# PCB-SSB-4x2.net
KiCad netlist of a schematic drawn in EAGLE
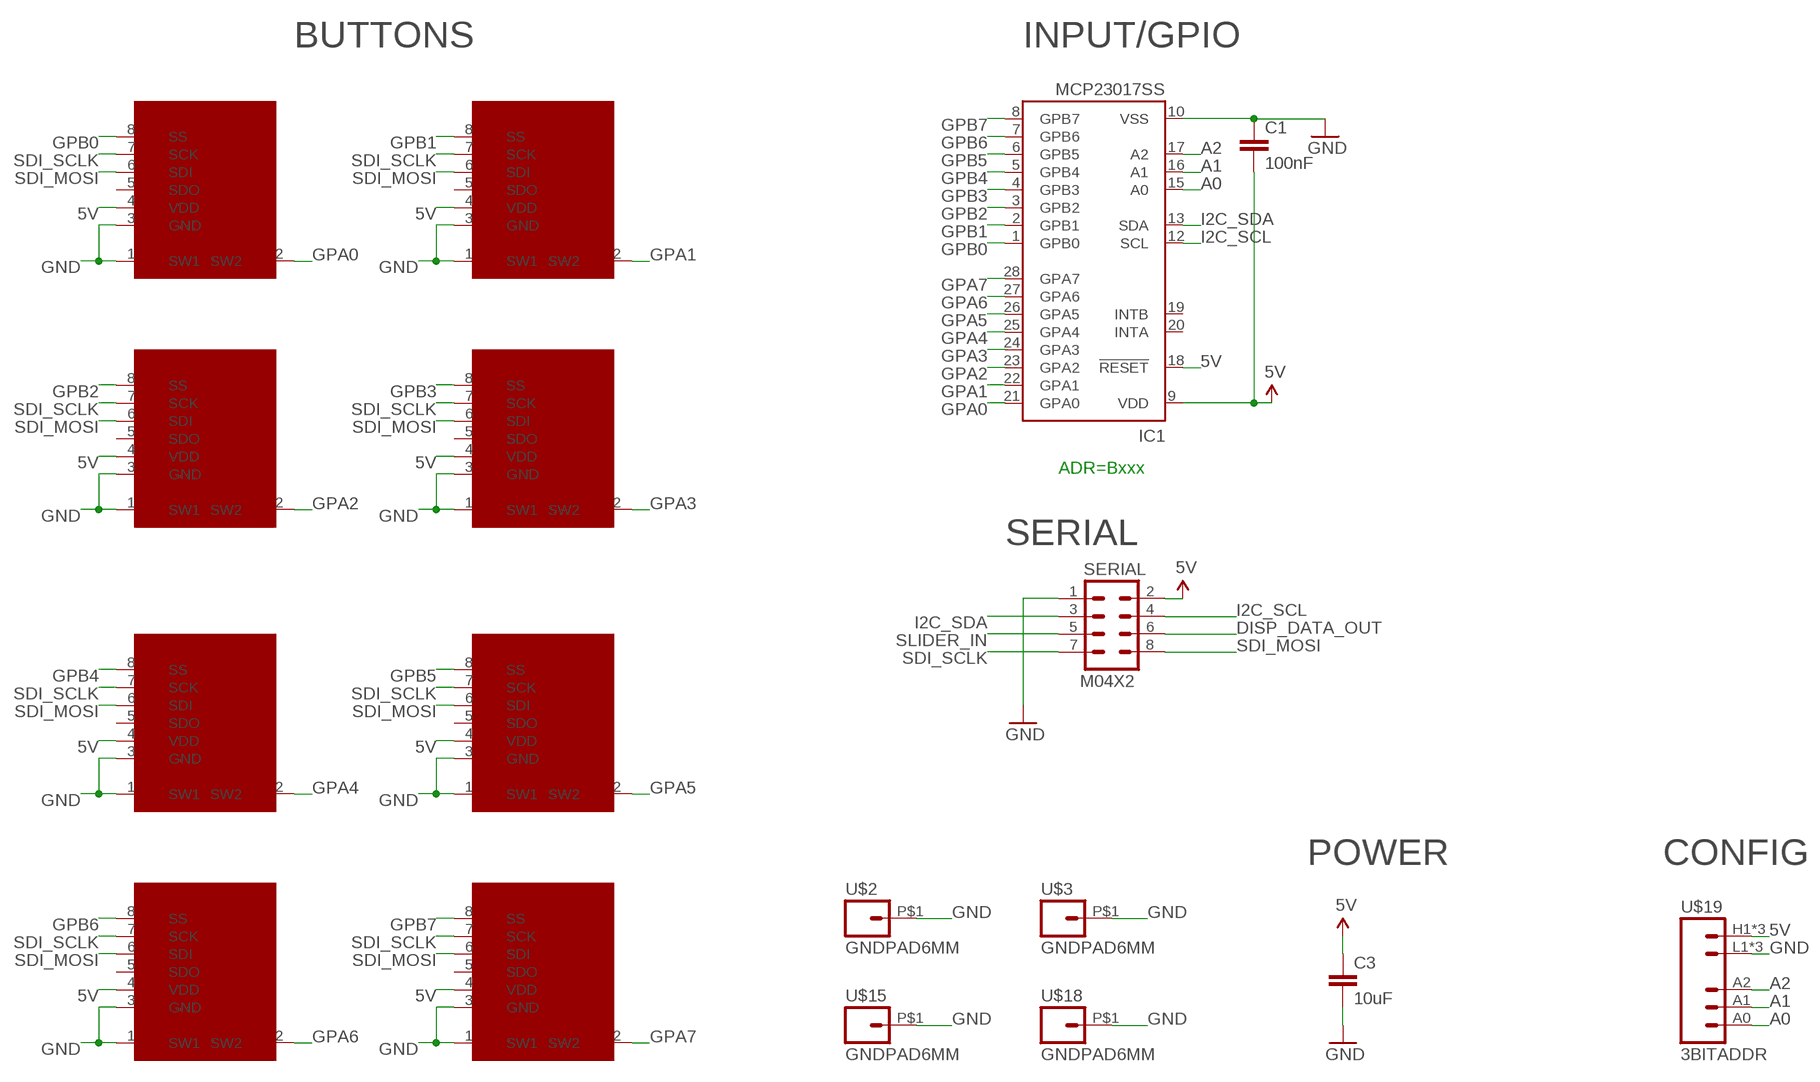
[diagram p0: schematic, sheet 1]

(export (version "E")
  (design (tool "Eeschema 10.0.6"))
  (components
    (comp (ref "C1")
      (value "100nF")
      (footprint "eagle-import:0603-CAP")
      (libsource (lib "eagle-import") (part "CAP0603-CAP"))
    )
    (comp (ref "C3")
      (value "10uF")
      (footprint "eagle-import:0805")
      (libsource (lib "eagle-import") (part "CAP0805"))
    )
    (comp (ref "IC1")
      (value "MCP23017SS")
      (footprint "eagle-import:SSOP28")
      (fields
        (field (name "MF") "MICROCHIP")
        (field (name "MPN") "MCP23017-E/SS")
        (field (name "MPN_1") "MCP23017-E/SS")
        (field (name "OC_FARNELL") "1467674")
        (field (name "OC_NEWARK") "31K2960")
      )
      (libsource (lib "eagle-import") (part "MCP23017SS"))
    )
    (comp (ref "SERIAL")
      (value "M04X2")
      (footprint "eagle-import:2X4")
      (libsource (lib "eagle-import") (part "M04X2"))
    )
    (comp (ref "SSW1")
      (value "SMART_SWITCHSMART_SWITCH_8PIN")
      (footprint "eagle-import:SMART_SWITCH")
      (libsource (lib "eagle-import") (part "SMART_SWITCHSMART_SWITCH_8PIN"))
    )
    (comp (ref "SSW2")
      (value "SMART_SWITCHSMART_SWITCH_8PIN")
      (footprint "eagle-import:SMART_SWITCH")
      (libsource (lib "eagle-import") (part "SMART_SWITCHSMART_SWITCH_8PIN"))
    )
    (comp (ref "SSW3")
      (value "SMART_SWITCHSMART_SWITCH_8PIN")
      (footprint "eagle-import:SMART_SWITCH")
      (libsource (lib "eagle-import") (part "SMART_SWITCHSMART_SWITCH_8PIN"))
    )
    (comp (ref "SSW4")
      (value "SMART_SWITCHSMART_SWITCH_8PIN")
      (footprint "eagle-import:SMART_SWITCH")
      (libsource (lib "eagle-import") (part "SMART_SWITCHSMART_SWITCH_8PIN"))
    )
    (comp (ref "SSW5")
      (value "SMART_SWITCHSMART_SWITCH_8PIN")
      (footprint "eagle-import:SMART_SWITCH")
      (libsource (lib "eagle-import") (part "SMART_SWITCHSMART_SWITCH_8PIN"))
    )
    (comp (ref "SSW6")
      (value "SMART_SWITCHSMART_SWITCH_8PIN")
      (footprint "eagle-import:SMART_SWITCH")
      (libsource (lib "eagle-import") (part "SMART_SWITCHSMART_SWITCH_8PIN"))
    )
    (comp (ref "SSW7")
      (value "SMART_SWITCHSMART_SWITCH_8PIN")
      (footprint "eagle-import:SMART_SWITCH")
      (libsource (lib "eagle-import") (part "SMART_SWITCHSMART_SWITCH_8PIN"))
    )
    (comp (ref "SSW8")
      (value "SMART_SWITCHSMART_SWITCH_8PIN")
      (footprint "eagle-import:SMART_SWITCH")
      (libsource (lib "eagle-import") (part "SMART_SWITCHSMART_SWITCH_8PIN"))
    )
    (comp (ref "U$2")
      (value "GNDPAD6MM")
      (footprint "eagle-import:3.2MMPAD6MM")
      (libsource (lib "eagle-import") (part "GNDPAD6MM"))
    )
    (comp (ref "U$3")
      (value "GNDPAD6MM")
      (footprint "eagle-import:3.2MMPAD6MM")
      (libsource (lib "eagle-import") (part "GNDPAD6MM"))
    )
    (comp (ref "U$15")
      (value "GNDPAD6MM")
      (footprint "eagle-import:3.2MMPAD6MM")
      (libsource (lib "eagle-import") (part "GNDPAD6MM"))
    )
    (comp (ref "U$18")
      (value "GNDPAD6MM")
      (footprint "eagle-import:3.2MMPAD6MM")
      (libsource (lib "eagle-import") (part "GNDPAD6MM"))
    )
    (comp (ref "U$19")
      (value "3BITADDR")
      (footprint "eagle-import:3BITADDR")
      (libsource (lib "eagle-import") (part "3BITADDR"))
    )
  )
  (nets
    (net (code "1") (name "/A0") (class "Default")
      (node (ref "IC1") (pin "15") (pinfunction "A0_15") (pintype "input"))
      (node (ref "U$19") (pin "A0") (pinfunction "A0_A0") (pintype "passive"))
    )
    (net (code "2") (name "/A1") (class "Default")
      (node (ref "IC1") (pin "16") (pinfunction "A1_16") (pintype "input"))
      (node (ref "U$19") (pin "A1") (pinfunction "A1_A1") (pintype "passive"))
    )
    (net (code "3") (name "/A2") (class "Default")
      (node (ref "IC1") (pin "17") (pinfunction "A2_17") (pintype "input"))
      (node (ref "U$19") (pin "A2") (pinfunction "A2_A2") (pintype "passive"))
    )
    (net (code "4") (name "/DISP_DATA_OUT") (class "Default")
      (node (ref "SERIAL") (pin "6") (pinfunction "6_6") (pintype "passive"))
    )
    (net (code "5") (name "/GPA0") (class "Default")
      (node (ref "IC1") (pin "21") (pinfunction "GPA0_21") (pintype "bidirectional"))
      (node (ref "SSW1") (pin "2") (pinfunction "SW2_2") (pintype "bidirectional"))
    )
    (net (code "6") (name "/GPA1") (class "Default")
      (node (ref "IC1") (pin "22") (pinfunction "GPA1_22") (pintype "bidirectional"))
      (node (ref "SSW2") (pin "2") (pinfunction "SW2_2") (pintype "bidirectional"))
    )
    (net (code "7") (name "/GPA2") (class "Default")
      (node (ref "IC1") (pin "23") (pinfunction "GPA2_23") (pintype "bidirectional"))
      (node (ref "SSW3") (pin "2") (pinfunction "SW2_2") (pintype "bidirectional"))
    )
    (net (code "8") (name "/GPA3") (class "Default")
      (node (ref "IC1") (pin "24") (pinfunction "GPA3_24") (pintype "bidirectional"))
      (node (ref "SSW4") (pin "2") (pinfunction "SW2_2") (pintype "bidirectional"))
    )
    (net (code "9") (name "/GPA4") (class "Default")
      (node (ref "IC1") (pin "25") (pinfunction "GPA4_25") (pintype "bidirectional"))
      (node (ref "SSW5") (pin "2") (pinfunction "SW2_2") (pintype "bidirectional"))
    )
    (net (code "10") (name "/GPA5") (class "Default")
      (node (ref "IC1") (pin "26") (pinfunction "GPA5_26") (pintype "bidirectional"))
      (node (ref "SSW6") (pin "2") (pinfunction "SW2_2") (pintype "bidirectional"))
    )
    (net (code "11") (name "/GPA6") (class "Default")
      (node (ref "IC1") (pin "27") (pinfunction "GPA6_27") (pintype "bidirectional"))
      (node (ref "SSW7") (pin "2") (pinfunction "SW2_2") (pintype "bidirectional"))
    )
    (net (code "12") (name "/GPA7") (class "Default")
      (node (ref "IC1") (pin "28") (pinfunction "GPA7_28") (pintype "bidirectional"))
      (node (ref "SSW8") (pin "2") (pinfunction "SW2_2") (pintype "bidirectional"))
    )
    (net (code "13") (name "/GPB0") (class "Default")
      (node (ref "IC1") (pin "1") (pinfunction "GPB0_1") (pintype "bidirectional"))
      (node (ref "SSW1") (pin "8") (pinfunction "SS_8") (pintype "bidirectional"))
    )
    (net (code "14") (name "/GPB1") (class "Default")
      (node (ref "IC1") (pin "2") (pinfunction "GPB1_2") (pintype "bidirectional"))
      (node (ref "SSW2") (pin "8") (pinfunction "SS_8") (pintype "bidirectional"))
    )
    (net (code "15") (name "/GPB2") (class "Default")
      (node (ref "IC1") (pin "3") (pinfunction "GPB2_3") (pintype "bidirectional"))
      (node (ref "SSW3") (pin "8") (pinfunction "SS_8") (pintype "bidirectional"))
    )
    (net (code "16") (name "/GPB3") (class "Default")
      (node (ref "IC1") (pin "4") (pinfunction "GPB3_4") (pintype "bidirectional"))
      (node (ref "SSW4") (pin "8") (pinfunction "SS_8") (pintype "bidirectional"))
    )
    (net (code "17") (name "/GPB4") (class "Default")
      (node (ref "IC1") (pin "5") (pinfunction "GPB4_5") (pintype "bidirectional"))
      (node (ref "SSW5") (pin "8") (pinfunction "SS_8") (pintype "bidirectional"))
    )
    (net (code "18") (name "/GPB5") (class "Default")
      (node (ref "IC1") (pin "6") (pinfunction "GPB5_6") (pintype "bidirectional"))
      (node (ref "SSW6") (pin "8") (pinfunction "SS_8") (pintype "bidirectional"))
    )
    (net (code "19") (name "/GPB6") (class "Default")
      (node (ref "IC1") (pin "7") (pinfunction "GPB6_7") (pintype "bidirectional"))
      (node (ref "SSW7") (pin "8") (pinfunction "SS_8") (pintype "bidirectional"))
    )
    (net (code "20") (name "/GPB7") (class "Default")
      (node (ref "IC1") (pin "8") (pinfunction "GPB7_8") (pintype "bidirectional"))
      (node (ref "SSW8") (pin "8") (pinfunction "SS_8") (pintype "bidirectional"))
    )
    (net (code "21") (name "/I2C_SCL") (class "Default")
      (node (ref "IC1") (pin "12") (pinfunction "SCL_12") (pintype "input"))
      (node (ref "SERIAL") (pin "4") (pinfunction "4_4") (pintype "passive"))
    )
    (net (code "22") (name "/I2C_SDA") (class "Default")
      (node (ref "IC1") (pin "13") (pinfunction "SDA_13") (pintype "bidirectional"))
      (node (ref "SERIAL") (pin "3") (pinfunction "3_3") (pintype "passive"))
    )
    (net (code "23") (name "/SDI_MOSI") (class "Default")
      (node (ref "SERIAL") (pin "8") (pinfunction "8_8") (pintype "passive"))
      (node (ref "SSW1") (pin "6") (pinfunction "SDI_6") (pintype "bidirectional"))
      (node (ref "SSW2") (pin "6") (pinfunction "SDI_6") (pintype "bidirectional"))
      (node (ref "SSW3") (pin "6") (pinfunction "SDI_6") (pintype "bidirectional"))
      (node (ref "SSW4") (pin "6") (pinfunction "SDI_6") (pintype "bidirectional"))
      (node (ref "SSW5") (pin "6") (pinfunction "SDI_6") (pintype "bidirectional"))
      (node (ref "SSW6") (pin "6") (pinfunction "SDI_6") (pintype "bidirectional"))
      (node (ref "SSW7") (pin "6") (pinfunction "SDI_6") (pintype "bidirectional"))
      (node (ref "SSW8") (pin "6") (pinfunction "SDI_6") (pintype "bidirectional"))
    )
    (net (code "24") (name "/SDI_SCLK") (class "Default")
      (node (ref "SERIAL") (pin "7") (pinfunction "7_7") (pintype "passive"))
      (node (ref "SSW1") (pin "7") (pinfunction "SCK_7") (pintype "bidirectional"))
      (node (ref "SSW2") (pin "7") (pinfunction "SCK_7") (pintype "bidirectional"))
      (node (ref "SSW3") (pin "7") (pinfunction "SCK_7") (pintype "bidirectional"))
      (node (ref "SSW4") (pin "7") (pinfunction "SCK_7") (pintype "bidirectional"))
      (node (ref "SSW5") (pin "7") (pinfunction "SCK_7") (pintype "bidirectional"))
      (node (ref "SSW6") (pin "7") (pinfunction "SCK_7") (pintype "bidirectional"))
      (node (ref "SSW7") (pin "7") (pinfunction "SCK_7") (pintype "bidirectional"))
      (node (ref "SSW8") (pin "7") (pinfunction "SCK_7") (pintype "bidirectional"))
    )
    (net (code "25") (name "/SLIDER_IN") (class "Default")
      (node (ref "SERIAL") (pin "5") (pinfunction "5_5") (pintype "passive"))
    )
    (net (code "26") (name "5V") (class "Default")
      (node (ref "C1") (pin "2") (pinfunction "2_2") (pintype "passive"))
      (node (ref "C3") (pin "1") (pinfunction "1_1") (pintype "passive"))
      (node (ref "IC1") (pin "18") (pinfunction "~{RESET}_18") (pintype "input"))
      (node (ref "IC1") (pin "9") (pinfunction "VDD_9") (pintype "power_in"))
      (node (ref "SERIAL") (pin "2") (pinfunction "2_2") (pintype "passive"))
      (node (ref "SSW1") (pin "4") (pinfunction "VDD_4") (pintype "bidirectional"))
      (node (ref "SSW2") (pin "4") (pinfunction "VDD_4") (pintype "bidirectional"))
      (node (ref "SSW3") (pin "4") (pinfunction "VDD_4") (pintype "bidirectional"))
      (node (ref "SSW4") (pin "4") (pinfunction "VDD_4") (pintype "bidirectional"))
      (node (ref "SSW5") (pin "4") (pinfunction "VDD_4") (pintype "bidirectional"))
      (node (ref "SSW6") (pin "4") (pinfunction "VDD_4") (pintype "bidirectional"))
      (node (ref "SSW7") (pin "4") (pinfunction "VDD_4") (pintype "bidirectional"))
      (node (ref "SSW8") (pin "4") (pinfunction "VDD_4") (pintype "bidirectional"))
      (node (ref "U$19") (pin "H1") (pinfunction "VCC_H1") (pintype "passive"))
      (node (ref "U$19") (pin "H2") (pinfunction "VCC_H2") (pintype "passive"))
      (node (ref "U$19") (pin "H3") (pinfunction "VCC_H3") (pintype "passive"))
    )
    (net (code "27") (name "GND") (class "Default")
      (node (ref "C1") (pin "1") (pinfunction "1_1") (pintype "passive"))
      (node (ref "C3") (pin "2") (pinfunction "2_2") (pintype "passive"))
      (node (ref "IC1") (pin "10") (pinfunction "VSS_10") (pintype "power_in"))
      (node (ref "SERIAL") (pin "1") (pinfunction "1_1") (pintype "passive"))
      (node (ref "SSW1") (pin "1") (pinfunction "SW1_1") (pintype "bidirectional"))
      (node (ref "SSW1") (pin "3") (pinfunction "GND_3") (pintype "bidirectional"))
      (node (ref "SSW2") (pin "1") (pinfunction "SW1_1") (pintype "bidirectional"))
      (node (ref "SSW2") (pin "3") (pinfunction "GND_3") (pintype "bidirectional"))
      (node (ref "SSW3") (pin "1") (pinfunction "SW1_1") (pintype "bidirectional"))
      (node (ref "SSW3") (pin "3") (pinfunction "GND_3") (pintype "bidirectional"))
      (node (ref "SSW4") (pin "1") (pinfunction "SW1_1") (pintype "bidirectional"))
      (node (ref "SSW4") (pin "3") (pinfunction "GND_3") (pintype "bidirectional"))
      (node (ref "SSW5") (pin "1") (pinfunction "SW1_1") (pintype "bidirectional"))
      (node (ref "SSW5") (pin "3") (pinfunction "GND_3") (pintype "bidirectional"))
      (node (ref "SSW6") (pin "1") (pinfunction "SW1_1") (pintype "bidirectional"))
      (node (ref "SSW6") (pin "3") (pinfunction "GND_3") (pintype "bidirectional"))
      (node (ref "SSW7") (pin "1") (pinfunction "SW1_1") (pintype "bidirectional"))
      (node (ref "SSW7") (pin "3") (pinfunction "GND_3") (pintype "bidirectional"))
      (node (ref "SSW8") (pin "1") (pinfunction "SW1_1") (pintype "bidirectional"))
      (node (ref "SSW8") (pin "3") (pinfunction "GND_3") (pintype "bidirectional"))
      (node (ref "U$15") (pin "P$1") (pinfunction "1_P$1") (pintype "passive"))
      (node (ref "U$18") (pin "P$1") (pinfunction "1_P$1") (pintype "passive"))
      (node (ref "U$19") (pin "L1") (pinfunction "GND_L1") (pintype "passive"))
      (node (ref "U$19") (pin "L2") (pinfunction "GND_L2") (pintype "passive"))
      (node (ref "U$19") (pin "L3") (pinfunction "GND_L3") (pintype "passive"))
      (node (ref "U$2") (pin "P$1") (pinfunction "1_P$1") (pintype "passive"))
      (node (ref "U$3") (pin "P$1") (pinfunction "1_P$1") (pintype "passive"))
    )
    (net (code "28") (name "unconnected-(IC1-INTA-Pad20)") (class "Default")
      (node (ref "IC1") (pin "20") (pinfunction "INTA_20") (pintype "output"))
    )
    (net (code "29") (name "unconnected-(IC1-INTB-Pad19)") (class "Default")
      (node (ref "IC1") (pin "19") (pinfunction "INTB_19") (pintype "output"))
    )
    (net (code "30") (name "unconnected-(SSW1-SDO-Pad5)") (class "Default")
      (node (ref "SSW1") (pin "5") (pinfunction "SDO_5") (pintype "bidirectional"))
    )
    (net (code "31") (name "unconnected-(SSW2-SDO-Pad5)") (class "Default")
      (node (ref "SSW2") (pin "5") (pinfunction "SDO_5") (pintype "bidirectional"))
    )
    (net (code "32") (name "unconnected-(SSW3-SDO-Pad5)") (class "Default")
      (node (ref "SSW3") (pin "5") (pinfunction "SDO_5") (pintype "bidirectional"))
    )
    (net (code "33") (name "unconnected-(SSW4-SDO-Pad5)") (class "Default")
      (node (ref "SSW4") (pin "5") (pinfunction "SDO_5") (pintype "bidirectional"))
    )
    (net (code "34") (name "unconnected-(SSW5-SDO-Pad5)") (class "Default")
      (node (ref "SSW5") (pin "5") (pinfunction "SDO_5") (pintype "bidirectional"))
    )
    (net (code "35") (name "unconnected-(SSW6-SDO-Pad5)") (class "Default")
      (node (ref "SSW6") (pin "5") (pinfunction "SDO_5") (pintype "bidirectional"))
    )
    (net (code "36") (name "unconnected-(SSW7-SDO-Pad5)") (class "Default")
      (node (ref "SSW7") (pin "5") (pinfunction "SDO_5") (pintype "bidirectional"))
    )
    (net (code "37") (name "unconnected-(SSW8-SDO-Pad5)") (class "Default")
      (node (ref "SSW8") (pin "5") (pinfunction "SDO_5") (pintype "bidirectional"))
    )
  )
)
